# Hardware-Neuron.net
KiCad netlist of a schematic drawn in EAGLE
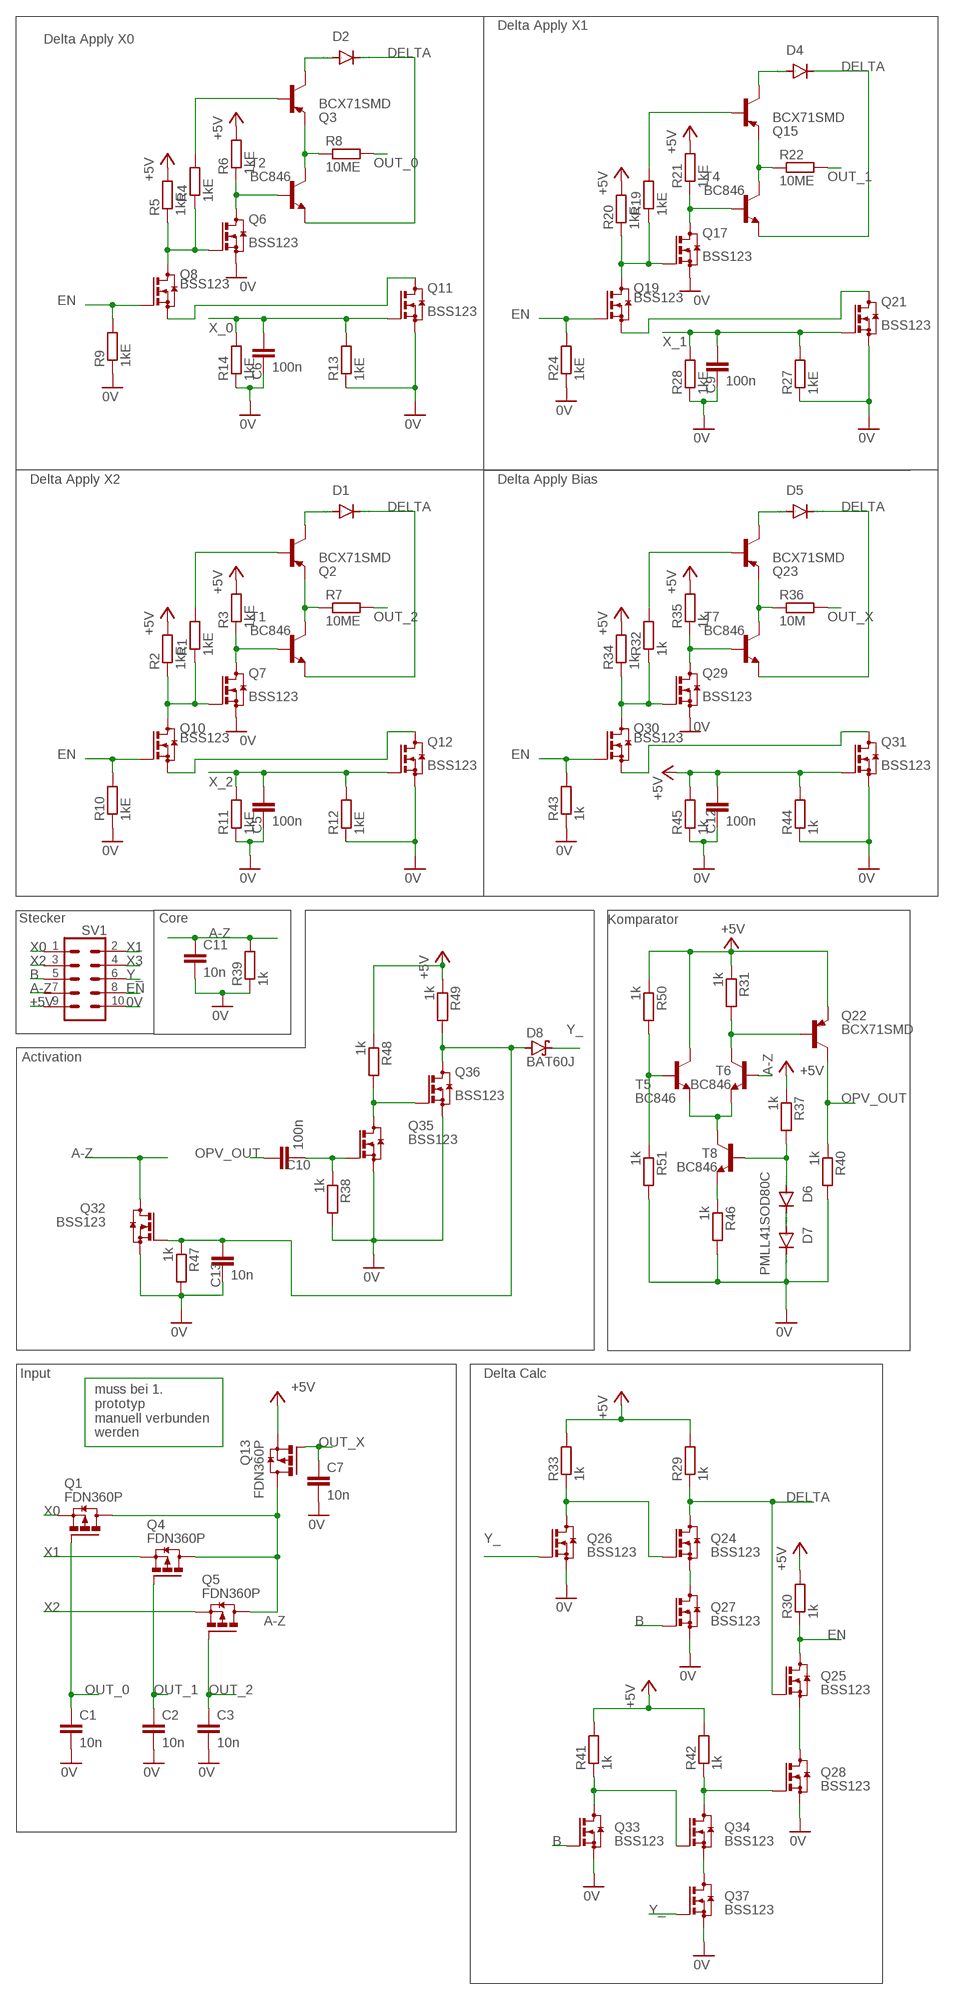
[diagram p0: schematic, sheet 1]

(export (version "E")
  (design (tool "Eeschema 10.0.6"))
  (components
    (comp (ref "C1")
      (value "10n")
      (footprint "eagle-import:C0805")
      (libsource (lib "eagle-import") (part "C-EUC0805"))
    )
    (comp (ref "C2")
      (value "10n")
      (footprint "eagle-import:C0805")
      (libsource (lib "eagle-import") (part "C-EUC0805"))
    )
    (comp (ref "C3")
      (value "10n")
      (footprint "eagle-import:C0805")
      (libsource (lib "eagle-import") (part "C-EUC0805"))
    )
    (comp (ref "C5")
      (value "100n")
      (footprint "eagle-import:C0805")
      (libsource (lib "eagle-import") (part "C-EUC0805"))
    )
    (comp (ref "C6")
      (value "100n")
      (footprint "eagle-import:C0805")
      (libsource (lib "eagle-import") (part "C-EUC0805"))
    )
    (comp (ref "C7")
      (value "10n")
      (footprint "eagle-import:C0805")
      (libsource (lib "eagle-import") (part "C-EUC0805"))
    )
    (comp (ref "C9")
      (value "100n")
      (footprint "eagle-import:C0805")
      (libsource (lib "eagle-import") (part "C-EUC0805"))
    )
    (comp (ref "C10")
      (value "100n")
      (footprint "eagle-import:C0805")
      (libsource (lib "eagle-import") (part "C-EUC0805"))
    )
    (comp (ref "C11")
      (value "10n")
      (footprint "eagle-import:C0805")
      (libsource (lib "eagle-import") (part "C-EUC0805"))
    )
    (comp (ref "C12")
      (value "100n")
      (footprint "eagle-import:C0805")
      (libsource (lib "eagle-import") (part "C-EUC0805"))
    )
    (comp (ref "C13")
      (value "10n")
      (footprint "eagle-import:C0805")
      (libsource (lib "eagle-import") (part "C-EUC0805"))
    )
    (comp (ref "D1")
      (value "PMLL41SOD80C")
      (footprint "eagle-import:SOD80C")
      (libsource (lib "eagle-import") (part "PMLL41SOD80C"))
    )
    (comp (ref "D2")
      (value "PMLL41SOD80C")
      (footprint "eagle-import:SOD80C")
      (libsource (lib "eagle-import") (part "PMLL41SOD80C"))
    )
    (comp (ref "D4")
      (value "PMLL41SOD80C")
      (footprint "eagle-import:SOD80C")
      (libsource (lib "eagle-import") (part "PMLL41SOD80C"))
    )
    (comp (ref "D5")
      (value "PMLL41SOD80C")
      (footprint "eagle-import:SOD80C")
      (libsource (lib "eagle-import") (part "PMLL41SOD80C"))
    )
    (comp (ref "D6")
      (value "PMLL41SOD80C")
      (footprint "eagle-import:SOD80C")
      (libsource (lib "eagle-import") (part "PMLL41SOD80C"))
    )
    (comp (ref "D7")
      (value "PMLL41SOD80C")
      (footprint "eagle-import:SOD80C")
      (libsource (lib "eagle-import") (part "PMLL41SOD80C"))
    )
    (comp (ref "D8")
      (value "BAT60J")
      (footprint "eagle-import:SOD323_ST")
      (libsource (lib "eagle-import") (part "BAT60J"))
    )
    (comp (ref "Q1")
      (value "FDN360P")
      (footprint "eagle-import:SUPER-SOT3")
      (libsource (lib "eagle-import") (part "FDN360P"))
    )
    (comp (ref "Q2")
      (value "BCX71SMD")
      (footprint "eagle-import:SOT23")
      (libsource (lib "eagle-import") (part "BCX71SMD"))
    )
    (comp (ref "Q3")
      (value "BCX71SMD")
      (footprint "eagle-import:SOT23")
      (libsource (lib "eagle-import") (part "BCX71SMD"))
    )
    (comp (ref "Q4")
      (value "FDN360P")
      (footprint "eagle-import:SUPER-SOT3")
      (libsource (lib "eagle-import") (part "FDN360P"))
    )
    (comp (ref "Q5")
      (value "FDN360P")
      (footprint "eagle-import:SUPER-SOT3")
      (libsource (lib "eagle-import") (part "FDN360P"))
    )
    (comp (ref "Q6")
      (value "BSS123")
      (footprint "eagle-import:SOT23")
      (libsource (lib "eagle-import") (part "BSS123"))
    )
    (comp (ref "Q7")
      (value "BSS123")
      (footprint "eagle-import:SOT23")
      (libsource (lib "eagle-import") (part "BSS123"))
    )
    (comp (ref "Q8")
      (value "BSS123")
      (footprint "eagle-import:SOT23")
      (libsource (lib "eagle-import") (part "BSS123"))
    )
    (comp (ref "Q10")
      (value "BSS123")
      (footprint "eagle-import:SOT23")
      (libsource (lib "eagle-import") (part "BSS123"))
    )
    (comp (ref "Q11")
      (value "BSS123")
      (footprint "eagle-import:SOT23")
      (libsource (lib "eagle-import") (part "BSS123"))
    )
    (comp (ref "Q12")
      (value "BSS123")
      (footprint "eagle-import:SOT23")
      (libsource (lib "eagle-import") (part "BSS123"))
    )
    (comp (ref "Q13")
      (value "FDN360P")
      (footprint "eagle-import:SUPER-SOT3")
      (libsource (lib "eagle-import") (part "FDN360P"))
    )
    (comp (ref "Q15")
      (value "BCX71SMD")
      (footprint "eagle-import:SOT23")
      (libsource (lib "eagle-import") (part "BCX71SMD"))
    )
    (comp (ref "Q17")
      (value "BSS123")
      (footprint "eagle-import:SOT23")
      (libsource (lib "eagle-import") (part "BSS123"))
    )
    (comp (ref "Q19")
      (value "BSS123")
      (footprint "eagle-import:SOT23")
      (libsource (lib "eagle-import") (part "BSS123"))
    )
    (comp (ref "Q21")
      (value "BSS123")
      (footprint "eagle-import:SOT23")
      (libsource (lib "eagle-import") (part "BSS123"))
    )
    (comp (ref "Q22")
      (value "BCX71SMD")
      (footprint "eagle-import:SOT23")
      (libsource (lib "eagle-import") (part "BCX71SMD"))
    )
    (comp (ref "Q23")
      (value "BCX71SMD")
      (footprint "eagle-import:SOT23")
      (libsource (lib "eagle-import") (part "BCX71SMD"))
    )
    (comp (ref "Q24")
      (value "BSS123")
      (footprint "eagle-import:SOT23")
      (libsource (lib "eagle-import") (part "BSS123"))
    )
    (comp (ref "Q25")
      (value "BSS123")
      (footprint "eagle-import:SOT23")
      (libsource (lib "eagle-import") (part "BSS123"))
    )
    (comp (ref "Q26")
      (value "BSS123")
      (footprint "eagle-import:SOT23")
      (libsource (lib "eagle-import") (part "BSS123"))
    )
    (comp (ref "Q27")
      (value "BSS123")
      (footprint "eagle-import:SOT23")
      (libsource (lib "eagle-import") (part "BSS123"))
    )
    (comp (ref "Q28")
      (value "BSS123")
      (footprint "eagle-import:SOT23")
      (libsource (lib "eagle-import") (part "BSS123"))
    )
    (comp (ref "Q29")
      (value "BSS123")
      (footprint "eagle-import:SOT23")
      (libsource (lib "eagle-import") (part "BSS123"))
    )
    (comp (ref "Q30")
      (value "BSS123")
      (footprint "eagle-import:SOT23")
      (libsource (lib "eagle-import") (part "BSS123"))
    )
    (comp (ref "Q31")
      (value "BSS123")
      (footprint "eagle-import:SOT23")
      (libsource (lib "eagle-import") (part "BSS123"))
    )
    (comp (ref "Q32")
      (value "BSS123")
      (footprint "eagle-import:SOT23")
      (libsource (lib "eagle-import") (part "BSS123"))
    )
    (comp (ref "Q33")
      (value "BSS123")
      (footprint "eagle-import:SOT23")
      (libsource (lib "eagle-import") (part "BSS123"))
    )
    (comp (ref "Q34")
      (value "BSS123")
      (footprint "eagle-import:SOT23")
      (libsource (lib "eagle-import") (part "BSS123"))
    )
    (comp (ref "Q35")
      (value "BSS123")
      (footprint "eagle-import:SOT23")
      (libsource (lib "eagle-import") (part "BSS123"))
    )
    (comp (ref "Q36")
      (value "BSS123")
      (footprint "eagle-import:SOT23")
      (libsource (lib "eagle-import") (part "BSS123"))
    )
    (comp (ref "Q37")
      (value "BSS123")
      (footprint "eagle-import:SOT23")
      (libsource (lib "eagle-import") (part "BSS123"))
    )
    (comp (ref "R1")
      (value "1kE")
      (footprint "eagle-import:M0805")
      (libsource (lib "eagle-import") (part "R-EU_M0805"))
    )
    (comp (ref "R2")
      (value "1kE")
      (footprint "eagle-import:M0805")
      (libsource (lib "eagle-import") (part "R-EU_M0805"))
    )
    (comp (ref "R3")
      (value "1kE")
      (footprint "eagle-import:M0805")
      (libsource (lib "eagle-import") (part "R-EU_M0805"))
    )
    (comp (ref "R4")
      (value "1kE")
      (footprint "eagle-import:M0805")
      (libsource (lib "eagle-import") (part "R-EU_M0805"))
    )
    (comp (ref "R5")
      (value "1kE")
      (footprint "eagle-import:M0805")
      (libsource (lib "eagle-import") (part "R-EU_M0805"))
    )
    (comp (ref "R6")
      (value "1kE")
      (footprint "eagle-import:M0805")
      (libsource (lib "eagle-import") (part "R-EU_M0805"))
    )
    (comp (ref "R7")
      (value "10ME")
      (footprint "eagle-import:M0805")
      (libsource (lib "eagle-import") (part "R-EU_M0805"))
    )
    (comp (ref "R8")
      (value "10ME")
      (footprint "eagle-import:M0805")
      (libsource (lib "eagle-import") (part "R-EU_M0805"))
    )
    (comp (ref "R9")
      (value "1kE")
      (footprint "eagle-import:M0805")
      (libsource (lib "eagle-import") (part "R-EU_M0805"))
    )
    (comp (ref "R10")
      (value "1kE")
      (footprint "eagle-import:M0805")
      (libsource (lib "eagle-import") (part "R-EU_M0805"))
    )
    (comp (ref "R11")
      (value "1kE")
      (footprint "eagle-import:M0805")
      (libsource (lib "eagle-import") (part "R-EU_M0805"))
    )
    (comp (ref "R12")
      (value "1kE")
      (footprint "eagle-import:M0805")
      (libsource (lib "eagle-import") (part "R-EU_M0805"))
    )
    (comp (ref "R13")
      (value "1kE")
      (footprint "eagle-import:M0805")
      (libsource (lib "eagle-import") (part "R-EU_M0805"))
    )
    (comp (ref "R14")
      (value "1kE")
      (footprint "eagle-import:M0805")
      (libsource (lib "eagle-import") (part "R-EU_M0805"))
    )
    (comp (ref "R19")
      (value "1kE")
      (footprint "eagle-import:M0805")
      (libsource (lib "eagle-import") (part "R-EU_M0805"))
    )
    (comp (ref "R20")
      (value "1kE")
      (footprint "eagle-import:M0805")
      (libsource (lib "eagle-import") (part "R-EU_M0805"))
    )
    (comp (ref "R21")
      (value "1kE")
      (footprint "eagle-import:M0805")
      (libsource (lib "eagle-import") (part "R-EU_M0805"))
    )
    (comp (ref "R22")
      (value "10ME")
      (footprint "eagle-import:M0805")
      (libsource (lib "eagle-import") (part "R-EU_M0805"))
    )
    (comp (ref "R24")
      (value "1kE")
      (footprint "eagle-import:M0805")
      (libsource (lib "eagle-import") (part "R-EU_M0805"))
    )
    (comp (ref "R27")
      (value "1kE")
      (footprint "eagle-import:M0805")
      (libsource (lib "eagle-import") (part "R-EU_M0805"))
    )
    (comp (ref "R28")
      (value "1kE")
      (footprint "eagle-import:M0805")
      (libsource (lib "eagle-import") (part "R-EU_M0805"))
    )
    (comp (ref "R29")
      (value "1k")
      (footprint "eagle-import:M0805")
      (libsource (lib "eagle-import") (part "R-EU_M0805"))
    )
    (comp (ref "R30")
      (value "1k")
      (footprint "eagle-import:M0805")
      (libsource (lib "eagle-import") (part "R-EU_M0805"))
    )
    (comp (ref "R31")
      (value "1k")
      (footprint "eagle-import:M0805")
      (libsource (lib "eagle-import") (part "R-EU_M0805"))
    )
    (comp (ref "R32")
      (value "1k")
      (footprint "eagle-import:M0805")
      (libsource (lib "eagle-import") (part "R-EU_M0805"))
    )
    (comp (ref "R33")
      (value "1k")
      (footprint "eagle-import:M0805")
      (libsource (lib "eagle-import") (part "R-EU_M0805"))
    )
    (comp (ref "R34")
      (value "1k")
      (footprint "eagle-import:M0805")
      (libsource (lib "eagle-import") (part "R-EU_M0805"))
    )
    (comp (ref "R35")
      (value "1k")
      (footprint "eagle-import:M0805")
      (libsource (lib "eagle-import") (part "R-EU_M0805"))
    )
    (comp (ref "R36")
      (value "10M")
      (footprint "eagle-import:M0805")
      (libsource (lib "eagle-import") (part "R-EU_M0805"))
    )
    (comp (ref "R37")
      (value "1k")
      (footprint "eagle-import:M0805")
      (libsource (lib "eagle-import") (part "R-EU_M0805"))
    )
    (comp (ref "R38")
      (value "1k")
      (footprint "eagle-import:M0805")
      (libsource (lib "eagle-import") (part "R-EU_M0805"))
    )
    (comp (ref "R39")
      (value "1k")
      (footprint "eagle-import:M0805")
      (libsource (lib "eagle-import") (part "R-EU_M0805"))
    )
    (comp (ref "R40")
      (value "1k")
      (footprint "eagle-import:M0805")
      (libsource (lib "eagle-import") (part "R-EU_M0805"))
    )
    (comp (ref "R41")
      (value "1k")
      (footprint "eagle-import:M0805")
      (libsource (lib "eagle-import") (part "R-EU_M0805"))
    )
    (comp (ref "R42")
      (value "1k")
      (footprint "eagle-import:M0805")
      (libsource (lib "eagle-import") (part "R-EU_M0805"))
    )
    (comp (ref "R43")
      (value "1k")
      (footprint "eagle-import:M0805")
      (libsource (lib "eagle-import") (part "R-EU_M0805"))
    )
    (comp (ref "R44")
      (value "1k")
      (footprint "eagle-import:M0805")
      (libsource (lib "eagle-import") (part "R-EU_M0805"))
    )
    (comp (ref "R45")
      (value "1k")
      (footprint "eagle-import:M0805")
      (libsource (lib "eagle-import") (part "R-EU_M0805"))
    )
    (comp (ref "R46")
      (value "1k")
      (footprint "eagle-import:M0805")
      (libsource (lib "eagle-import") (part "R-EU_M0805"))
    )
    (comp (ref "R47")
      (value "1k")
      (footprint "eagle-import:M0805")
      (libsource (lib "eagle-import") (part "R-EU_M0805"))
    )
    (comp (ref "R48")
      (value "1k")
      (footprint "eagle-import:M0805")
      (libsource (lib "eagle-import") (part "R-EU_M0805"))
    )
    (comp (ref "R49")
      (value "1k")
      (footprint "eagle-import:M0805")
      (libsource (lib "eagle-import") (part "R-EU_M0805"))
    )
    (comp (ref "R50")
      (value "1k")
      (footprint "eagle-import:M0805")
      (libsource (lib "eagle-import") (part "R-EU_M0805"))
    )
    (comp (ref "R51")
      (value "1k")
      (footprint "eagle-import:M0805")
      (libsource (lib "eagle-import") (part "R-EU_M0805"))
    )
    (comp (ref "SV1")
      (value "ML10")
      (footprint "eagle-import:ML10")
      (libsource (lib "eagle-import") (part "ML10"))
    )
    (comp (ref "T1")
      (value "BC846")
      (footprint "eagle-import:SOT23")
      (libsource (lib "eagle-import") (part "BC846"))
    )
    (comp (ref "T2")
      (value "BC846")
      (footprint "eagle-import:SOT23")
      (libsource (lib "eagle-import") (part "BC846"))
    )
    (comp (ref "T4")
      (value "BC846")
      (footprint "eagle-import:SOT23")
      (libsource (lib "eagle-import") (part "BC846"))
    )
    (comp (ref "T5")
      (value "BC846")
      (footprint "eagle-import:SOT23")
      (libsource (lib "eagle-import") (part "BC846"))
    )
    (comp (ref "T6")
      (value "BC846")
      (footprint "eagle-import:SOT23")
      (libsource (lib "eagle-import") (part "BC846"))
    )
    (comp (ref "T7")
      (value "BC846")
      (footprint "eagle-import:SOT23")
      (libsource (lib "eagle-import") (part "BC846"))
    )
    (comp (ref "T8")
      (value "BC846")
      (footprint "eagle-import:SOT23")
      (libsource (lib "eagle-import") (part "BC846"))
    )
  )
  (nets
    (net (code "1") (name "+5V") (class "Default")
      (node (ref "C12") (pin "1") (pinfunction "1_1") (pintype "passive"))
      (node (ref "Q13") (pin "2") (pinfunction "S_2") (pintype "passive"))
      (node (ref "Q22") (pin "2") (pinfunction "E_2") (pintype "passive"))
      (node (ref "Q31") (pin "1") (pinfunction "G_1") (pintype "passive"))
      (node (ref "R2") (pin "2") (pinfunction "2_2") (pintype "passive"))
      (node (ref "R20") (pin "2") (pinfunction "2_2") (pintype "passive"))
      (node (ref "R21") (pin "2") (pinfunction "2_2") (pintype "passive"))
      (node (ref "R29") (pin "2") (pinfunction "2_2") (pintype "passive"))
      (node (ref "R3") (pin "2") (pinfunction "2_2") (pintype "passive"))
      (node (ref "R30") (pin "2") (pinfunction "2_2") (pintype "passive"))
      (node (ref "R31") (pin "1") (pinfunction "1_1") (pintype "passive"))
      (node (ref "R33") (pin "2") (pinfunction "2_2") (pintype "passive"))
      (node (ref "R34") (pin "2") (pinfunction "2_2") (pintype "passive"))
      (node (ref "R35") (pin "2") (pinfunction "2_2") (pintype "passive"))
      (node (ref "R37") (pin "1") (pinfunction "1_1") (pintype "passive"))
      (node (ref "R41") (pin "2") (pinfunction "2_2") (pintype "passive"))
      (node (ref "R42") (pin "2") (pinfunction "2_2") (pintype "passive"))
      (node (ref "R44") (pin "2") (pinfunction "2_2") (pintype "passive"))
      (node (ref "R45") (pin "2") (pinfunction "2_2") (pintype "passive"))
      (node (ref "R48") (pin "1") (pinfunction "1_1") (pintype "passive"))
      (node (ref "R49") (pin "1") (pinfunction "1_1") (pintype "passive"))
      (node (ref "R5") (pin "2") (pinfunction "2_2") (pintype "passive"))
      (node (ref "R50") (pin "1") (pinfunction "1_1") (pintype "passive"))
      (node (ref "R6") (pin "2") (pinfunction "2_2") (pintype "passive"))
      (node (ref "SV1") (pin "9") (pinfunction "9_9") (pintype "passive"))
      (node (ref "T5") (pin "3") (pinfunction "C_3") (pintype "passive"))
    )
    (net (code "2") (name "/A-Z") (class "Default")
      (node (ref "C11") (pin "1") (pinfunction "1_1") (pintype "passive"))
      (node (ref "Q1") (pin "3") (pinfunction "D_3") (pintype "passive"))
      (node (ref "Q13") (pin "3") (pinfunction "D_3") (pintype "passive"))
      (node (ref "Q32") (pin "3") (pinfunction "D_3") (pintype "passive"))
      (node (ref "Q4") (pin "3") (pinfunction "D_3") (pintype "passive"))
      (node (ref "Q5") (pin "3") (pinfunction "D_3") (pintype "passive"))
      (node (ref "R39") (pin "2") (pinfunction "2_2") (pintype "passive"))
      (node (ref "SV1") (pin "7") (pinfunction "7_7") (pintype "passive"))
      (node (ref "T6") (pin "1") (pinfunction "B_1") (pintype "passive"))
    )
    (net (code "3") (name "/B") (class "Default")
      (node (ref "Q27") (pin "1") (pinfunction "G_1") (pintype "passive"))
      (node (ref "Q33") (pin "1") (pinfunction "G_1") (pintype "passive"))
      (node (ref "SV1") (pin "5") (pinfunction "5_5") (pintype "passive"))
    )
    (net (code "4") (name "/DELTA") (class "Default")
      (node (ref "D1") (pin "C") (pinfunction "C_C") (pintype "passive"))
      (node (ref "D2") (pin "C") (pinfunction "C_C") (pintype "passive"))
      (node (ref "D4") (pin "C") (pinfunction "C_C") (pintype "passive"))
      (node (ref "D5") (pin "C") (pinfunction "C_C") (pintype "passive"))
      (node (ref "Q24") (pin "3") (pinfunction "D_3") (pintype "passive"))
      (node (ref "Q25") (pin "1") (pinfunction "G_1") (pintype "passive"))
      (node (ref "R29") (pin "1") (pinfunction "1_1") (pintype "passive"))
      (node (ref "T1") (pin "2") (pinfunction "E_2") (pintype "passive"))
      (node (ref "T2") (pin "2") (pinfunction "E_2") (pintype "passive"))
      (node (ref "T4") (pin "2") (pinfunction "E_2") (pintype "passive"))
      (node (ref "T7") (pin "2") (pinfunction "E_2") (pintype "passive"))
    )
    (net (code "5") (name "/EN") (class "Default")
      (node (ref "Q10") (pin "1") (pinfunction "G_1") (pintype "passive"))
      (node (ref "Q19") (pin "1") (pinfunction "G_1") (pintype "passive"))
      (node (ref "Q25") (pin "3") (pinfunction "D_3") (pintype "passive"))
      (node (ref "Q30") (pin "1") (pinfunction "G_1") (pintype "passive"))
      (node (ref "Q8") (pin "1") (pinfunction "G_1") (pintype "passive"))
      (node (ref "R10") (pin "2") (pinfunction "2_2") (pintype "passive"))
      (node (ref "R24") (pin "2") (pinfunction "2_2") (pintype "passive"))
      (node (ref "R30") (pin "1") (pinfunction "1_1") (pintype "passive"))
      (node (ref "R43") (pin "2") (pinfunction "2_2") (pintype "passive"))
      (node (ref "R9") (pin "2") (pinfunction "2_2") (pintype "passive"))
      (node (ref "SV1") (pin "8") (pinfunction "8_8") (pintype "passive"))
    )
    (net (code "6") (name "/OPV_OUT") (class "Default")
      (node (ref "C10") (pin "1") (pinfunction "1_1") (pintype "passive"))
      (node (ref "Q22") (pin "3") (pinfunction "C_3") (pintype "passive"))
      (node (ref "R40") (pin "1") (pinfunction "1_1") (pintype "passive"))
    )
    (net (code "7") (name "/OUT_0") (class "Default")
      (node (ref "C1") (pin "1") (pinfunction "1_1") (pintype "passive"))
      (node (ref "Q1") (pin "1") (pinfunction "G_1") (pintype "passive"))
      (node (ref "R8") (pin "2") (pinfunction "2_2") (pintype "passive"))
    )
    (net (code "8") (name "/OUT_1") (class "Default")
      (node (ref "C2") (pin "1") (pinfunction "1_1") (pintype "passive"))
      (node (ref "Q4") (pin "1") (pinfunction "G_1") (pintype "passive"))
      (node (ref "R22") (pin "2") (pinfunction "2_2") (pintype "passive"))
    )
    (net (code "9") (name "/OUT_2") (class "Default")
      (node (ref "C3") (pin "1") (pinfunction "1_1") (pintype "passive"))
      (node (ref "Q5") (pin "1") (pinfunction "G_1") (pintype "passive"))
      (node (ref "R7") (pin "2") (pinfunction "2_2") (pintype "passive"))
    )
    (net (code "10") (name "/OUT_X") (class "Default")
      (node (ref "C7") (pin "1") (pinfunction "1_1") (pintype "passive"))
      (node (ref "Q13") (pin "1") (pinfunction "G_1") (pintype "passive"))
      (node (ref "R36") (pin "2") (pinfunction "2_2") (pintype "passive"))
    )
    (net (code "11") (name "/X0") (class "Default")
      (node (ref "Q1") (pin "2") (pinfunction "S_2") (pintype "passive"))
      (node (ref "SV1") (pin "1") (pinfunction "1_1") (pintype "passive"))
    )
    (net (code "12") (name "/X1") (class "Default")
      (node (ref "Q4") (pin "2") (pinfunction "S_2") (pintype "passive"))
      (node (ref "SV1") (pin "2") (pinfunction "2_2") (pintype "passive"))
    )
    (net (code "13") (name "/X2") (class "Default")
      (node (ref "Q5") (pin "2") (pinfunction "S_2") (pintype "passive"))
      (node (ref "SV1") (pin "3") (pinfunction "3_3") (pintype "passive"))
    )
    (net (code "14") (name "/X3") (class "Default")
      (node (ref "SV1") (pin "4") (pinfunction "4_4") (pintype "passive"))
    )
    (net (code "15") (name "/X_0") (class "Default")
      (node (ref "C6") (pin "1") (pinfunction "1_1") (pintype "passive"))
      (node (ref "Q11") (pin "1") (pinfunction "G_1") (pintype "passive"))
      (node (ref "R13") (pin "2") (pinfunction "2_2") (pintype "passive"))
      (node (ref "R14") (pin "2") (pinfunction "2_2") (pintype "passive"))
    )
    (net (code "16") (name "/X_1") (class "Default")
      (node (ref "C9") (pin "1") (pinfunction "1_1") (pintype "passive"))
      (node (ref "Q21") (pin "1") (pinfunction "G_1") (pintype "passive"))
      (node (ref "R27") (pin "2") (pinfunction "2_2") (pintype "passive"))
      (node (ref "R28") (pin "2") (pinfunction "2_2") (pintype "passive"))
    )
    (net (code "17") (name "/X_2") (class "Default")
      (node (ref "C5") (pin "1") (pinfunction "1_1") (pintype "passive"))
      (node (ref "Q12") (pin "1") (pinfunction "G_1") (pintype "passive"))
      (node (ref "R11") (pin "2") (pinfunction "2_2") (pintype "passive"))
      (node (ref "R12") (pin "2") (pinfunction "2_2") (pintype "passive"))
    )
    (net (code "18") (name "/Y_") (class "Default")
      (node (ref "D8") (pin "C") (pinfunction "C_C") (pintype "passive"))
      (node (ref "Q26") (pin "1") (pinfunction "G_1") (pintype "passive"))
      (node (ref "Q37") (pin "1") (pinfunction "G_1") (pintype "passive"))
      (node (ref "SV1") (pin "6") (pinfunction "6_6") (pintype "passive"))
    )
    (net (code "19") (name "0V") (class "Default")
      (node (ref "C1") (pin "2") (pinfunction "2_2") (pintype "passive"))
      (node (ref "C11") (pin "2") (pinfunction "2_2") (pintype "passive"))
      (node (ref "C12") (pin "2") (pinfunction "2_2") (pintype "passive"))
      (node (ref "C13") (pin "2") (pinfunction "2_2") (pintype "passive"))
      (node (ref "C2") (pin "2") (pinfunction "2_2") (pintype "passive"))
      (node (ref "C3") (pin "2") (pinfunction "2_2") (pintype "passive"))
      (node (ref "C5") (pin "2") (pinfunction "2_2") (pintype "passive"))
      (node (ref "C6") (pin "2") (pinfunction "2_2") (pintype "passive"))
      (node (ref "C7") (pin "2") (pinfunction "2_2") (pintype "passive"))
      (node (ref "C9") (pin "2") (pinfunction "2_2") (pintype "passive"))
      (node (ref "D7") (pin "C") (pinfunction "C_C") (pintype "passive"))
      (node (ref "Q11") (pin "2") (pinfunction "S_2") (pintype "passive"))
      (node (ref "Q12") (pin "2") (pinfunction "S_2") (pintype "passive"))
      (node (ref "Q17") (pin "2") (pinfunction "S_2") (pintype "passive"))
      (node (ref "Q21") (pin "2") (pinfunction "S_2") (pintype "passive"))
      (node (ref "Q26") (pin "2") (pinfunction "S_2") (pintype "passive"))
      (node (ref "Q27") (pin "2") (pinfunction "S_2") (pintype "passive"))
      (node (ref "Q28") (pin "2") (pinfunction "S_2") (pintype "passive"))
      (node (ref "Q29") (pin "2") (pinfunction "S_2") (pintype "passive"))
      (node (ref "Q31") (pin "2") (pinfunction "S_2") (pintype "passive"))
      (node (ref "Q32") (pin "2") (pinfunction "S_2") (pintype "passive"))
      (node (ref "Q33") (pin "2") (pinfunction "S_2") (pintype "passive"))
      (node (ref "Q35") (pin "2") (pinfunction "S_2") (pintype "passive"))
      (node (ref "Q36") (pin "2") (pinfunction "S_2") (pintype "passive"))
      (node (ref "Q37") (pin "2") (pinfunction "S_2") (pintype "passive"))
      (node (ref "Q6") (pin "2") (pinfunction "S_2") (pintype "passive"))
      (node (ref "Q7") (pin "2") (pinfunction "S_2") (pintype "passive"))
      (node (ref "R10") (pin "1") (pinfunction "1_1") (pintype "passive"))
      (node (ref "R11") (pin "1") (pinfunction "1_1") (pintype "passive"))
      (node (ref "R12") (pin "1") (pinfunction "1_1") (pintype "passive"))
      (node (ref "R13") (pin "1") (pinfunction "1_1") (pintype "passive"))
      (node (ref "R14") (pin "1") (pinfunction "1_1") (pintype "passive"))
      (node (ref "R24") (pin "1") (pinfunction "1_1") (pintype "passive"))
      (node (ref "R27") (pin "1") (pinfunction "1_1") (pintype "passive"))
      (node (ref "R28") (pin "1") (pinfunction "1_1") (pintype "passive"))
      (node (ref "R38") (pin "2") (pinfunction "2_2") (pintype "passive"))
      (node (ref "R39") (pin "1") (pinfunction "1_1") (pintype "passive"))
      (node (ref "R40") (pin "2") (pinfunction "2_2") (pintype "passive"))
      (node (ref "R43") (pin "1") (pinfunction "1_1") (pintype "passive"))
      (node (ref "R44") (pin "1") (pinfunction "1_1") (pintype "passive"))
      (node (ref "R45") (pin "1") (pinfunction "1_1") (pintype "passive"))
      (node (ref "R46") (pin "2") (pinfunction "2_2") (pintype "passive"))
      (node (ref "R47") (pin "2") (pinfunction "2_2") (pintype "passive"))
      (node (ref "R51") (pin "2") (pinfunction "2_2") (pintype "passive"))
      (node (ref "R9") (pin "1") (pinfunction "1_1") (pintype "passive"))
      (node (ref "SV1") (pin "10") (pinfunction "10_10") (pintype "passive"))
    )
    (net (code "20") (name "Net-(D6-PadC)") (class "Default")
      (node (ref "D6") (pin "C") (pinfunction "C_C") (pintype "passive"))
      (node (ref "D7") (pin "A") (pinfunction "A_A") (pintype "passive"))
    )
    (net (code "21") (name "Net-(Q2-B)") (class "Default")
      (node (ref "Q2") (pin "1") (pinfunction "B_1") (pintype "passive"))
      (node (ref "R1") (pin "2") (pinfunction "2_2") (pintype "passive"))
    )
    (net (code "22") (name "Net-(Q2-C)") (class "Default")
      (node (ref "D1") (pin "A") (pinfunction "A_A") (pintype "passive"))
      (node (ref "Q2") (pin "3") (pinfunction "C_3") (pintype "passive"))
    )
    (net (code "23") (name "Net-(Q2-E)") (class "Default")
      (node (ref "Q2") (pin "2") (pinfunction "E_2") (pintype "passive"))
      (node (ref "R7") (pin "1") (pinfunction "1_1") (pintype "passive"))
      (node (ref "T1") (pin "3") (pinfunction "C_3") (pintype "passive"))
    )
    (net (code "24") (name "Net-(Q3-B)") (class "Default")
      (node (ref "Q3") (pin "1") (pinfunction "B_1") (pintype "passive"))
      (node (ref "R4") (pin "2") (pinfunction "2_2") (pintype "passive"))
    )
    (net (code "25") (name "Net-(Q3-C)") (class "Default")
      (node (ref "D2") (pin "A") (pinfunction "A_A") (pintype "passive"))
      (node (ref "Q3") (pin "3") (pinfunction "C_3") (pintype "passive"))
    )
    (net (code "26") (name "Net-(Q3-E)") (class "Default")
      (node (ref "Q3") (pin "2") (pinfunction "E_2") (pintype "passive"))
      (node (ref "R8") (pin "1") (pinfunction "1_1") (pintype "passive"))
      (node (ref "T2") (pin "3") (pinfunction "C_3") (pintype "passive"))
    )
    (net (code "27") (name "Net-(Q6-D)") (class "Default")
      (node (ref "Q6") (pin "3") (pinfunction "D_3") (pintype "passive"))
      (node (ref "R6") (pin "1") (pinfunction "1_1") (pintype "passive"))
      (node (ref "T2") (pin "1") (pinfunction "B_1") (pintype "passive"))
    )
    (net (code "28") (name "Net-(Q6-G)") (class "Default")
      (node (ref "Q6") (pin "1") (pinfunction "G_1") (pintype "passive"))
      (node (ref "Q8") (pin "3") (pinfunction "D_3") (pintype "passive"))
      (node (ref "R4") (pin "1") (pinfunction "1_1") (pintype "passive"))
      (node (ref "R5") (pin "1") (pinfunction "1_1") (pintype "passive"))
    )
    (net (code "29") (name "Net-(Q7-D)") (class "Default")
      (node (ref "Q7") (pin "3") (pinfunction "D_3") (pintype "passive"))
      (node (ref "R3") (pin "1") (pinfunction "1_1") (pintype "passive"))
      (node (ref "T1") (pin "1") (pinfunction "B_1") (pintype "passive"))
    )
    (net (code "30") (name "Net-(Q10-D)") (class "Default")
      (node (ref "Q10") (pin "3") (pinfunction "D_3") (pintype "passive"))
      (node (ref "Q7") (pin "1") (pinfunction "G_1") (pintype "passive"))
      (node (ref "R1") (pin "1") (pinfunction "1_1") (pintype "passive"))
      (node (ref "R2") (pin "1") (pinfunction "1_1") (pintype "passive"))
    )
    (net (code "31") (name "Net-(Q10-S)") (class "Default")
      (node (ref "Q10") (pin "2") (pinfunction "S_2") (pintype "passive"))
      (node (ref "Q12") (pin "3") (pinfunction "D_3") (pintype "passive"))
    )
    (net (code "32") (name "Net-(Q11-D)") (class "Default")
      (node (ref "Q11") (pin "3") (pinfunction "D_3") (pintype "passive"))
      (node (ref "Q8") (pin "2") (pinfunction "S_2") (pintype "passive"))
    )
    (net (code "33") (name "Net-(Q15-B)") (class "Default")
      (node (ref "Q15") (pin "1") (pinfunction "B_1") (pintype "passive"))
      (node (ref "R19") (pin "2") (pinfunction "2_2") (pintype "passive"))
    )
    (net (code "34") (name "Net-(Q15-C)") (class "Default")
      (node (ref "D4") (pin "A") (pinfunction "A_A") (pintype "passive"))
      (node (ref "Q15") (pin "3") (pinfunction "C_3") (pintype "passive"))
    )
    (net (code "35") (name "Net-(Q15-E)") (class "Default")
      (node (ref "Q15") (pin "2") (pinfunction "E_2") (pintype "passive"))
      (node (ref "R22") (pin "1") (pinfunction "1_1") (pintype "passive"))
      (node (ref "T4") (pin "3") (pinfunction "C_3") (pintype "passive"))
    )
    (net (code "36") (name "Net-(Q17-D)") (class "Default")
      (node (ref "Q17") (pin "3") (pinfunction "D_3") (pintype "passive"))
      (node (ref "R21") (pin "1") (pinfunction "1_1") (pintype "passive"))
      (node (ref "T4") (pin "1") (pinfunction "B_1") (pintype "passive"))
    )
    (net (code "37") (name "Net-(Q17-G)") (class "Default")
      (node (ref "Q17") (pin "1") (pinfunction "G_1") (pintype "passive"))
      (node (ref "Q19") (pin "3") (pinfunction "D_3") (pintype "passive"))
      (node (ref "R19") (pin "1") (pinfunction "1_1") (pintype "passive"))
      (node (ref "R20") (pin "1") (pinfunction "1_1") (pintype "passive"))
    )
    (net (code "38") (name "Net-(Q19-S)") (class "Default")
      (node (ref "Q19") (pin "2") (pinfunction "S_2") (pintype "passive"))
      (node (ref "Q21") (pin "3") (pinfunction "D_3") (pintype "passive"))
    )
    (net (code "39") (name "Net-(Q22-B)") (class "Default")
      (node (ref "Q22") (pin "1") (pinfunction "B_1") (pintype "passive"))
      (node (ref "R31") (pin "2") (pinfunction "2_2") (pintype "passive"))
      (node (ref "T6") (pin "3") (pinfunction "C_3") (pintype "passive"))
    )
    (net (code "40") (name "Net-(Q23-B)") (class "Default")
      (node (ref "Q23") (pin "1") (pinfunction "B_1") (pintype "passive"))
      (node (ref "R32") (pin "2") (pinfunction "2_2") (pintype "passive"))
    )
    (net (code "41") (name "Net-(Q23-C)") (class "Default")
      (node (ref "D5") (pin "A") (pinfunction "A_A") (pintype "passive"))
      (node (ref "Q23") (pin "3") (pinfunction "C_3") (pintype "passive"))
    )
    (net (code "42") (name "Net-(Q23-E)") (class "Default")
      (node (ref "Q23") (pin "2") (pinfunction "E_2") (pintype "passive"))
      (node (ref "R36") (pin "1") (pinfunction "1_1") (pintype "passive"))
      (node (ref "T7") (pin "3") (pinfunction "C_3") (pintype "passive"))
    )
    (net (code "43") (name "Net-(Q24-G)") (class "Default")
      (node (ref "Q24") (pin "1") (pinfunction "G_1") (pintype "passive"))
      (node (ref "Q26") (pin "3") (pinfunction "D_3") (pintype "passive"))
      (node (ref "R33") (pin "1") (pinfunction "1_1") (pintype "passive"))
    )
    (net (code "44") (name "Net-(Q24-S)") (class "Default")
      (node (ref "Q24") (pin "2") (pinfunction "S_2") (pintype "passive"))
      (node (ref "Q27") (pin "3") (pinfunction "D_3") (pintype "passive"))
    )
    (net (code "45") (name "Net-(Q25-S)") (class "Default")
      (node (ref "Q25") (pin "2") (pinfunction "S_2") (pintype "passive"))
      (node (ref "Q28") (pin "3") (pinfunction "D_3") (pintype "passive"))
    )
    (net (code "46") (name "Net-(Q28-G)") (class "Default")
      (node (ref "Q28") (pin "1") (pinfunction "G_1") (pintype "passive"))
      (node (ref "Q34") (pin "3") (pinfunction "D_3") (pintype "passive"))
      (node (ref "R42") (pin "1") (pinfunction "1_1") (pintype "passive"))
    )
    (net (code "47") (name "Net-(Q29-D)") (class "Default")
      (node (ref "Q29") (pin "3") (pinfunction "D_3") (pintype "passive"))
      (node (ref "R35") (pin "1") (pinfunction "1_1") (pintype "passive"))
      (node (ref "T7") (pin "1") (pinfunction "B_1") (pintype "passive"))
    )
    (net (code "48") (name "Net-(Q29-G)") (class "Default")
      (node (ref "Q29") (pin "1") (pinfunction "G_1") (pintype "passive"))
      (node (ref "Q30") (pin "3") (pinfunction "D_3") (pintype "passive"))
      (node (ref "R32") (pin "1") (pinfunction "1_1") (pintype "passive"))
      (node (ref "R34") (pin "1") (pinfunction "1_1") (pintype "passive"))
    )
    (net (code "49") (name "Net-(Q30-S)") (class "Default")
      (node (ref "Q30") (pin "2") (pinfunction "S_2") (pintype "passive"))
      (node (ref "Q31") (pin "3") (pinfunction "D_3") (pintype "passive"))
    )
    (net (code "50") (name "Net-(Q32-G)") (class "Default")
      (node (ref "C13") (pin "1") (pinfunction "1_1") (pintype "passive"))
      (node (ref "D8") (pin "A") (pinfunction "A_A") (pintype "passive"))
      (node (ref "Q32") (pin "1") (pinfunction "G_1") (pintype "passive"))
      (node (ref "Q36") (pin "3") (pinfunction "D_3") (pintype "passive"))
      (node (ref "R47") (pin "1") (pinfunction "1_1") (pintype "passive"))
      (node (ref "R49") (pin "2") (pinfunction "2_2") (pintype "passive"))
    )
    (net (code "51") (name "Net-(Q33-D)") (class "Default")
      (node (ref "Q33") (pin "3") (pinfunction "D_3") (pintype "passive"))
      (node (ref "Q34") (pin "1") (pinfunction "G_1") (pintype "passive"))
      (node (ref "R41") (pin "1") (pinfunction "1_1") (pintype "passive"))
    )
    (net (code "52") (name "Net-(Q34-S)") (class "Default")
      (node (ref "Q34") (pin "2") (pinfunction "S_2") (pintype "passive"))
      (node (ref "Q37") (pin "3") (pinfunction "D_3") (pintype "passive"))
    )
    (net (code "53") (name "Net-(Q35-D)") (class "Default")
      (node (ref "Q35") (pin "3") (pinfunction "D_3") (pintype "passive"))
      (node (ref "Q36") (pin "1") (pinfunction "G_1") (pintype "passive"))
      (node (ref "R48") (pin "2") (pinfunction "2_2") (pintype "passive"))
    )
    (net (code "54") (name "Net-(Q35-G)") (class "Default")
      (node (ref "C10") (pin "2") (pinfunction "2_2") (pintype "passive"))
      (node (ref "Q35") (pin "1") (pinfunction "G_1") (pintype "passive"))
      (node (ref "R38") (pin "1") (pinfunction "1_1") (pintype "passive"))
    )
    (net (code "55") (name "Net-(T5-B)") (class "Default")
      (node (ref "R50") (pin "2") (pinfunction "2_2") (pintype "passive"))
      (node (ref "R51") (pin "1") (pinfunction "1_1") (pintype "passive"))
      (node (ref "T5") (pin "1") (pinfunction "B_1") (pintype "passive"))
    )
    (net (code "56") (name "Net-(T5-E)") (class "Default")
      (node (ref "T5") (pin "2") (pinfunction "E_2") (pintype "passive"))
      (node (ref "T6") (pin "2") (pinfunction "E_2") (pintype "passive"))
      (node (ref "T8") (pin "3") (pinfunction "C_3") (pintype "passive"))
    )
    (net (code "57") (name "Net-(T8-B)") (class "Default")
      (node (ref "D6") (pin "A") (pinfunction "A_A") (pintype "passive"))
      (node (ref "R37") (pin "2") (pinfunction "2_2") (pintype "passive"))
      (node (ref "T8") (pin "1") (pinfunction "B_1") (pintype "passive"))
    )
    (net (code "58") (name "Net-(T8-E)") (class "Default")
      (node (ref "R46") (pin "1") (pinfunction "1_1") (pintype "passive"))
      (node (ref "T8") (pin "2") (pinfunction "E_2") (pintype "passive"))
    )
  )
)
